# Relay_4_Channel.net
KiCad netlist of a schematic drawn in EAGLE
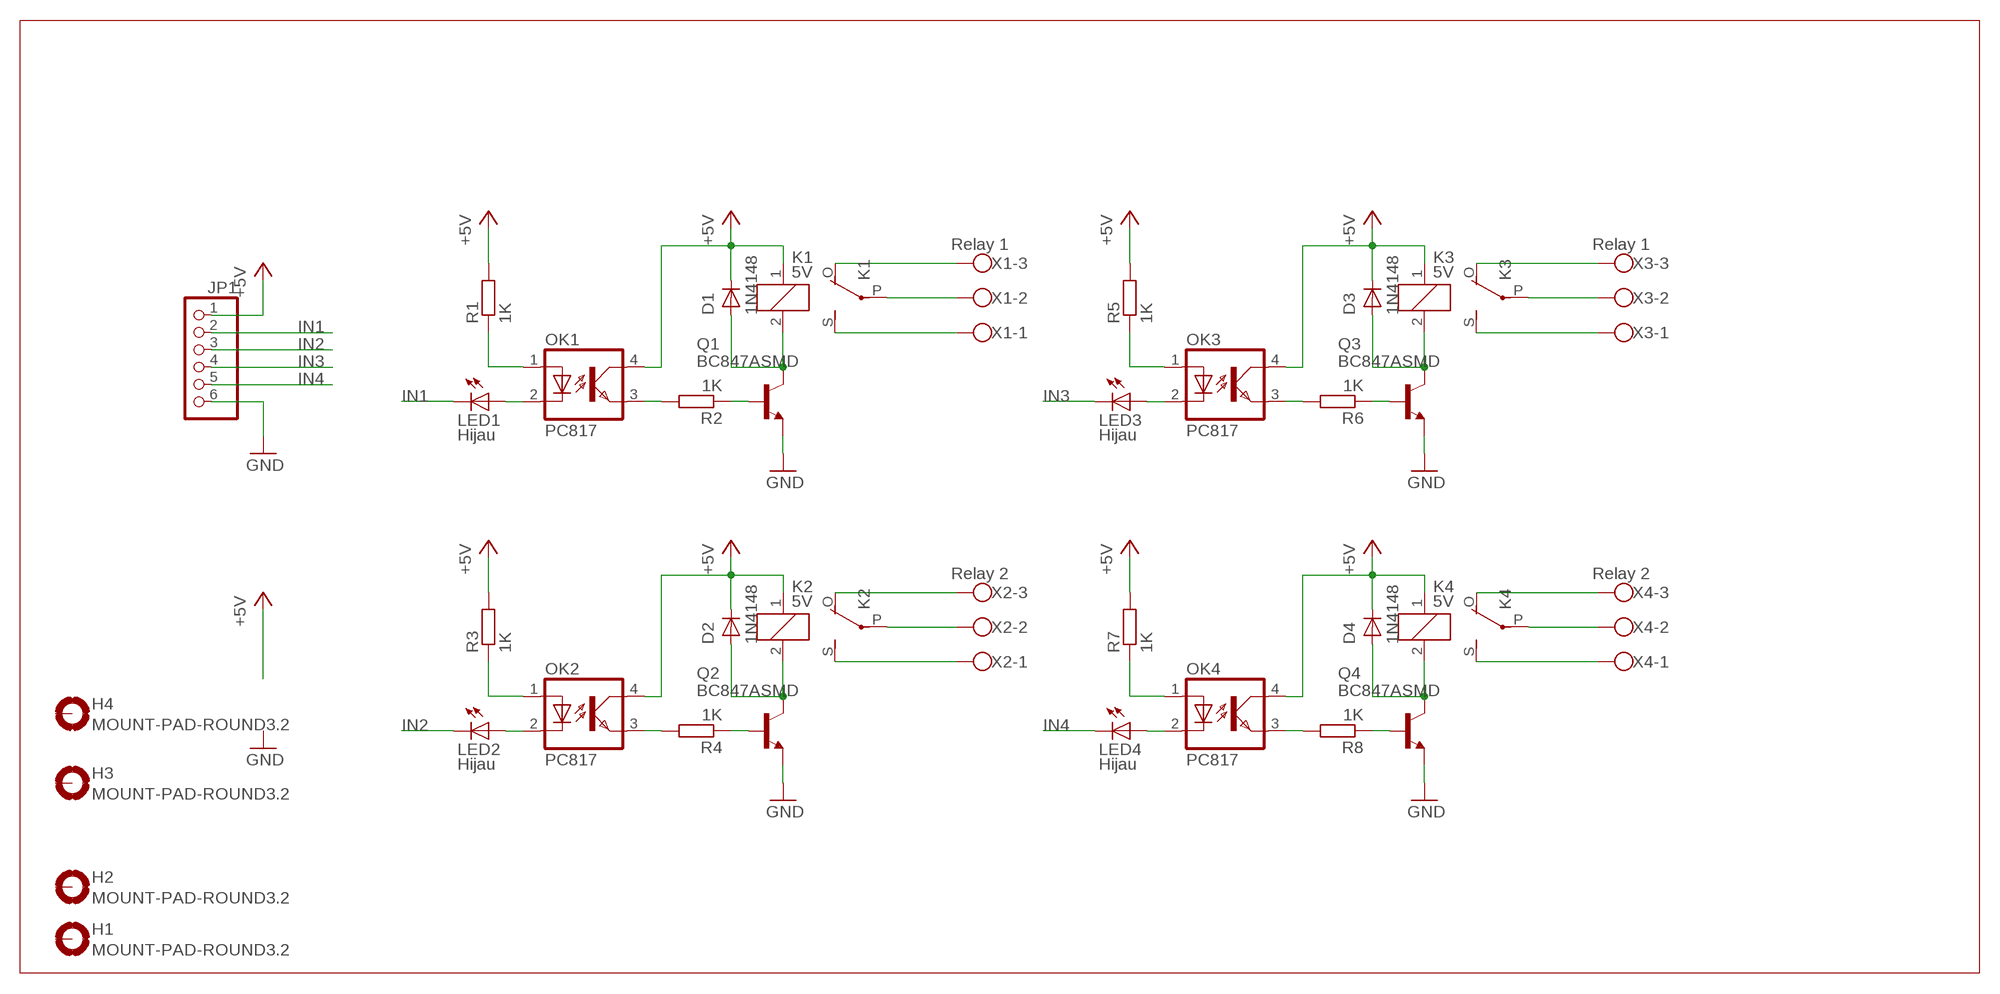
[diagram p0: schematic, sheet 1]

(export (version "E")
  (design (tool "Eeschema 10.0.6"))
  (components
    (comp (ref "D1")
      (value "1N4148")
      (footprint "eagle-import:SMA-DO214AC")
      (libsource (lib "eagle-import") (part "GF1"))
    )
    (comp (ref "D2")
      (value "1N4148")
      (footprint "eagle-import:SMA-DO214AC")
      (libsource (lib "eagle-import") (part "GF1"))
    )
    (comp (ref "D3")
      (value "1N4148")
      (footprint "eagle-import:SMA-DO214AC")
      (libsource (lib "eagle-import") (part "GF1"))
    )
    (comp (ref "D4")
      (value "1N4148")
      (footprint "eagle-import:SMA-DO214AC")
      (libsource (lib "eagle-import") (part "GF1"))
    )
    (comp (ref "H1")
      (value "MOUNT-PAD-ROUND3.2")
      (footprint "eagle-import:3,2-PAD")
      (libsource (lib "eagle-import") (part "MOUNT-PAD-ROUND3.2"))
    )
    (comp (ref "H2")
      (value "MOUNT-PAD-ROUND3.2")
      (footprint "eagle-import:3,2-PAD")
      (libsource (lib "eagle-import") (part "MOUNT-PAD-ROUND3.2"))
    )
    (comp (ref "H3")
      (value "MOUNT-PAD-ROUND3.2")
      (footprint "eagle-import:3,2-PAD")
      (libsource (lib "eagle-import") (part "MOUNT-PAD-ROUND3.2"))
    )
    (comp (ref "H4")
      (value "MOUNT-PAD-ROUND3.2")
      (footprint "eagle-import:3,2-PAD")
      (libsource (lib "eagle-import") (part "MOUNT-PAD-ROUND3.2"))
    )
    (comp (ref "JP1")
      (value "PINHD-1X6")
      (footprint "eagle-import:1X06")
      (libsource (lib "eagle-import") (part "PINHD-1X6"))
    )
    (comp (ref "K1")
      (value "5V")
      (footprint "eagle-import:ZF112")
      (libsource (lib "eagle-import") (part "ZF112"))
    )
    (comp (ref "K2")
      (value "5V")
      (footprint "eagle-import:ZF112")
      (libsource (lib "eagle-import") (part "ZF112"))
    )
    (comp (ref "K3")
      (value "5V")
      (footprint "eagle-import:ZF112")
      (libsource (lib "eagle-import") (part "ZF112"))
    )
    (comp (ref "K4")
      (value "5V")
      (footprint "eagle-import:ZF112")
      (libsource (lib "eagle-import") (part "ZF112"))
    )
    (comp (ref "LED1")
      (value "Hijau")
      (footprint "eagle-import:LED3MM")
      (libsource (lib "eagle-import") (part "LED3MM"))
    )
    (comp (ref "LED2")
      (value "Hijau")
      (footprint "eagle-import:LED3MM")
      (libsource (lib "eagle-import") (part "LED3MM"))
    )
    (comp (ref "LED3")
      (value "Hijau")
      (footprint "eagle-import:LED3MM")
      (libsource (lib "eagle-import") (part "LED3MM"))
    )
    (comp (ref "LED4")
      (value "Hijau")
      (footprint "eagle-import:LED3MM")
      (libsource (lib "eagle-import") (part "LED3MM"))
    )
    (comp (ref "OK1")
      (value "PC817")
      (footprint "eagle-import:DIL04")
      (fields (field (name "MPN") "PC817X4J000F"))
      (libsource (lib "eagle-import") (part "PC817"))
    )
    (comp (ref "OK2")
      (value "PC817")
      (footprint "eagle-import:DIL04")
      (fields (field (name "MPN") "PC817X4J000F"))
      (libsource (lib "eagle-import") (part "PC817"))
    )
    (comp (ref "OK3")
      (value "PC817")
      (footprint "eagle-import:DIL04")
      (fields (field (name "MPN") "PC817X4J000F"))
      (libsource (lib "eagle-import") (part "PC817"))
    )
    (comp (ref "OK4")
      (value "PC817")
      (footprint "eagle-import:DIL04")
      (fields (field (name "MPN") "PC817X4J000F"))
      (libsource (lib "eagle-import") (part "PC817"))
    )
    (comp (ref "Q1")
      (value "BC847ASMD")
      (footprint "eagle-import:SOT23")
      (libsource (lib "eagle-import") (part "BC847SMDA"))
    )
    (comp (ref "Q2")
      (value "BC847ASMD")
      (footprint "eagle-import:SOT23")
      (libsource (lib "eagle-import") (part "BC847SMDA"))
    )
    (comp (ref "Q3")
      (value "BC847ASMD")
      (footprint "eagle-import:SOT23")
      (libsource (lib "eagle-import") (part "BC847SMDA"))
    )
    (comp (ref "Q4")
      (value "BC847ASMD")
      (footprint "eagle-import:SOT23")
      (libsource (lib "eagle-import") (part "BC847SMDA"))
    )
    (comp (ref "R1")
      (value "1K")
      (footprint "eagle-import:R1206")
      (libsource (lib "eagle-import") (part "R-EU_R1206"))
    )
    (comp (ref "R2")
      (value "1K")
      (footprint "eagle-import:R1206")
      (libsource (lib "eagle-import") (part "R-EU_R1206"))
    )
    (comp (ref "R3")
      (value "1K")
      (footprint "eagle-import:R1206")
      (libsource (lib "eagle-import") (part "R-EU_R1206"))
    )
    (comp (ref "R4")
      (value "1K")
      (footprint "eagle-import:R1206")
      (libsource (lib "eagle-import") (part "R-EU_R1206"))
    )
    (comp (ref "R5")
      (value "1K")
      (footprint "eagle-import:R1206")
      (libsource (lib "eagle-import") (part "R-EU_R1206"))
    )
    (comp (ref "R6")
      (value "1K")
      (footprint "eagle-import:R1206")
      (libsource (lib "eagle-import") (part "R-EU_R1206"))
    )
    (comp (ref "R7")
      (value "1K")
      (footprint "eagle-import:R1206")
      (libsource (lib "eagle-import") (part "R-EU_R1206"))
    )
    (comp (ref "R8")
      (value "1K")
      (footprint "eagle-import:R1206")
      (libsource (lib "eagle-import") (part "R-EU_R1206"))
    )
    (comp (ref "X1")
      (value "Relay 1")
      (footprint "eagle-import:W237-103")
      (fields (field (name "MPN") "237-103"))
      (libsource (lib "eagle-import") (part "W237-103"))
    )
    (comp (ref "X2")
      (value "Relay 2")
      (footprint "eagle-import:W237-103")
      (fields (field (name "MPN") "237-103"))
      (libsource (lib "eagle-import") (part "W237-103"))
    )
    (comp (ref "X3")
      (value "Relay 1")
      (footprint "eagle-import:W237-103")
      (fields (field (name "MPN") "237-103"))
      (libsource (lib "eagle-import") (part "W237-103"))
    )
    (comp (ref "X4")
      (value "Relay 2")
      (footprint "eagle-import:W237-103")
      (fields (field (name "MPN") "237-103"))
      (libsource (lib "eagle-import") (part "W237-103"))
    )
  )
  (nets
    (net (code "1") (name "+5V") (class "Default")
      (node (ref "D1") (pin "K") (pinfunction "C_K") (pintype "passive"))
      (node (ref "D2") (pin "K") (pinfunction "C_K") (pintype "passive"))
      (node (ref "D3") (pin "K") (pinfunction "C_K") (pintype "passive"))
      (node (ref "D4") (pin "K") (pinfunction "C_K") (pintype "passive"))
      (node (ref "JP1") (pin "1") (pinfunction "1_1") (pintype "passive"))
      (node (ref "K1") (pin "1") (pinfunction "1_1") (pintype "passive"))
      (node (ref "K2") (pin "1") (pinfunction "1_1") (pintype "passive"))
      (node (ref "K3") (pin "1") (pinfunction "1_1") (pintype "passive"))
      (node (ref "K4") (pin "1") (pinfunction "1_1") (pintype "passive"))
      (node (ref "OK1") (pin "4") (pinfunction "COL_4") (pintype "passive"))
      (node (ref "OK2") (pin "4") (pinfunction "COL_4") (pintype "passive"))
      (node (ref "OK3") (pin "4") (pinfunction "COL_4") (pintype "passive"))
      (node (ref "OK4") (pin "4") (pinfunction "COL_4") (pintype "passive"))
      (node (ref "R1") (pin "2") (pinfunction "2_2") (pintype "passive"))
      (node (ref "R3") (pin "2") (pinfunction "2_2") (pintype "passive"))
      (node (ref "R5") (pin "2") (pinfunction "2_2") (pintype "passive"))
      (node (ref "R7") (pin "2") (pinfunction "2_2") (pintype "passive"))
    )
    (net (code "2") (name "/IN1") (class "Default")
      (node (ref "JP1") (pin "2") (pinfunction "2_2") (pintype "passive"))
      (node (ref "LED1") (pin "K") (pinfunction "C_K") (pintype "passive"))
    )
    (net (code "3") (name "/IN2") (class "Default")
      (node (ref "JP1") (pin "3") (pinfunction "3_3") (pintype "passive"))
      (node (ref "LED2") (pin "K") (pinfunction "C_K") (pintype "passive"))
    )
    (net (code "4") (name "/IN3") (class "Default")
      (node (ref "JP1") (pin "4") (pinfunction "4_4") (pintype "passive"))
      (node (ref "LED3") (pin "K") (pinfunction "C_K") (pintype "passive"))
    )
    (net (code "5") (name "/IN4") (class "Default")
      (node (ref "JP1") (pin "5") (pinfunction "5_5") (pintype "passive"))
      (node (ref "LED4") (pin "K") (pinfunction "C_K") (pintype "passive"))
    )
    (net (code "6") (name "GND") (class "Default")
      (node (ref "JP1") (pin "6") (pinfunction "6_6") (pintype "passive"))
      (node (ref "Q1") (pin "2") (pinfunction "E_2") (pintype "passive"))
      (node (ref "Q2") (pin "2") (pinfunction "E_2") (pintype "passive"))
      (node (ref "Q3") (pin "2") (pinfunction "E_2") (pintype "passive"))
      (node (ref "Q4") (pin "2") (pinfunction "E_2") (pintype "passive"))
    )
    (net (code "7") (name "Net-(OK1-A)") (class "Default")
      (node (ref "OK1") (pin "1") (pinfunction "A_1") (pintype "passive"))
      (node (ref "R1") (pin "1") (pinfunction "1_1") (pintype "passive"))
    )
    (net (code "8") (name "Net-(OK1-C)") (class "Default")
      (node (ref "LED1") (pin "A") (pinfunction "A_A") (pintype "passive"))
      (node (ref "OK1") (pin "2") (pinfunction "C_2") (pintype "passive"))
    )
    (net (code "9") (name "Net-(OK1-EMIT)") (class "Default")
      (node (ref "OK1") (pin "3") (pinfunction "EMIT_3") (pintype "passive"))
      (node (ref "R2") (pin "2") (pinfunction "2_2") (pintype "passive"))
    )
    (net (code "10") (name "Net-(OK2-A)") (class "Default")
      (node (ref "OK2") (pin "1") (pinfunction "A_1") (pintype "passive"))
      (node (ref "R3") (pin "1") (pinfunction "1_1") (pintype "passive"))
    )
    (net (code "11") (name "Net-(OK2-C)") (class "Default")
      (node (ref "LED2") (pin "A") (pinfunction "A_A") (pintype "passive"))
      (node (ref "OK2") (pin "2") (pinfunction "C_2") (pintype "passive"))
    )
    (net (code "12") (name "Net-(OK2-EMIT)") (class "Default")
      (node (ref "OK2") (pin "3") (pinfunction "EMIT_3") (pintype "passive"))
      (node (ref "R4") (pin "2") (pinfunction "2_2") (pintype "passive"))
    )
    (net (code "13") (name "Net-(OK3-A)") (class "Default")
      (node (ref "OK3") (pin "1") (pinfunction "A_1") (pintype "passive"))
      (node (ref "R5") (pin "1") (pinfunction "1_1") (pintype "passive"))
    )
    (net (code "14") (name "Net-(OK3-C)") (class "Default")
      (node (ref "LED3") (pin "A") (pinfunction "A_A") (pintype "passive"))
      (node (ref "OK3") (pin "2") (pinfunction "C_2") (pintype "passive"))
    )
    (net (code "15") (name "Net-(OK3-EMIT)") (class "Default")
      (node (ref "OK3") (pin "3") (pinfunction "EMIT_3") (pintype "passive"))
      (node (ref "R6") (pin "2") (pinfunction "2_2") (pintype "passive"))
    )
    (net (code "16") (name "Net-(OK4-A)") (class "Default")
      (node (ref "OK4") (pin "1") (pinfunction "A_1") (pintype "passive"))
      (node (ref "R7") (pin "1") (pinfunction "1_1") (pintype "passive"))
    )
    (net (code "17") (name "Net-(OK4-C)") (class "Default")
      (node (ref "LED4") (pin "A") (pinfunction "A_A") (pintype "passive"))
      (node (ref "OK4") (pin "2") (pinfunction "C_2") (pintype "passive"))
    )
    (net (code "18") (name "Net-(OK4-EMIT)") (class "Default")
      (node (ref "OK4") (pin "3") (pinfunction "EMIT_3") (pintype "passive"))
      (node (ref "R8") (pin "2") (pinfunction "2_2") (pintype "passive"))
    )
    (net (code "19") (name "Net-(Q1-B)") (class "Default")
      (node (ref "Q1") (pin "1") (pinfunction "B_1") (pintype "passive"))
      (node (ref "R2") (pin "1") (pinfunction "1_1") (pintype "passive"))
    )
    (net (code "20") (name "Net-(Q1-C)") (class "Default")
      (node (ref "D1") (pin "A") (pinfunction "A_A") (pintype "passive"))
      (node (ref "K1") (pin "2") (pinfunction "2_2") (pintype "passive"))
      (node (ref "Q1") (pin "3") (pinfunction "C_3") (pintype "passive"))
    )
    (net (code "21") (name "Net-(Q2-B)") (class "Default")
      (node (ref "Q2") (pin "1") (pinfunction "B_1") (pintype "passive"))
      (node (ref "R4") (pin "1") (pinfunction "1_1") (pintype "passive"))
    )
    (net (code "22") (name "Net-(Q2-C)") (class "Default")
      (node (ref "D2") (pin "A") (pinfunction "A_A") (pintype "passive"))
      (node (ref "K2") (pin "2") (pinfunction "2_2") (pintype "passive"))
      (node (ref "Q2") (pin "3") (pinfunction "C_3") (pintype "passive"))
    )
    (net (code "23") (name "Net-(Q3-B)") (class "Default")
      (node (ref "Q3") (pin "1") (pinfunction "B_1") (pintype "passive"))
      (node (ref "R6") (pin "1") (pinfunction "1_1") (pintype "passive"))
    )
    (net (code "24") (name "Net-(Q3-C)") (class "Default")
      (node (ref "D3") (pin "A") (pinfunction "A_A") (pintype "passive"))
      (node (ref "K3") (pin "2") (pinfunction "2_2") (pintype "passive"))
      (node (ref "Q3") (pin "3") (pinfunction "C_3") (pintype "passive"))
    )
    (net (code "25") (name "Net-(Q4-B)") (class "Default")
      (node (ref "Q4") (pin "1") (pinfunction "B_1") (pintype "passive"))
      (node (ref "R8") (pin "1") (pinfunction "1_1") (pintype "passive"))
    )
    (net (code "26") (name "Net-(Q4-C)") (class "Default")
      (node (ref "D4") (pin "A") (pinfunction "A_A") (pintype "passive"))
      (node (ref "K4") (pin "2") (pinfunction "2_2") (pintype "passive"))
      (node (ref "Q4") (pin "3") (pinfunction "C_3") (pintype "passive"))
    )
    (net (code "27") (name "Net-(X1A-KL)") (class "Default")
      (node (ref "K1") (pin "S") (pinfunction "S_S") (pintype "passive"))
      (node (ref "X1") (pin "1") (pinfunction "KL_1") (pintype "passive"))
    )
    (net (code "28") (name "Net-(X1B-KL)") (class "Default")
      (node (ref "K1") (pin "P") (pinfunction "P_P") (pintype "passive"))
      (node (ref "X1") (pin "2") (pinfunction "KL_2") (pintype "passive"))
    )
    (net (code "29") (name "Net-(X1C-KL)") (class "Default")
      (node (ref "K1") (pin "O") (pinfunction "O_O") (pintype "passive"))
      (node (ref "X1") (pin "3") (pinfunction "KL_3") (pintype "passive"))
    )
    (net (code "30") (name "Net-(X2A-KL)") (class "Default")
      (node (ref "K2") (pin "S") (pinfunction "S_S") (pintype "passive"))
      (node (ref "X2") (pin "1") (pinfunction "KL_1") (pintype "passive"))
    )
    (net (code "31") (name "Net-(X2B-KL)") (class "Default")
      (node (ref "K2") (pin "P") (pinfunction "P_P") (pintype "passive"))
      (node (ref "X2") (pin "2") (pinfunction "KL_2") (pintype "passive"))
    )
    (net (code "32") (name "Net-(X2C-KL)") (class "Default")
      (node (ref "K2") (pin "O") (pinfunction "O_O") (pintype "passive"))
      (node (ref "X2") (pin "3") (pinfunction "KL_3") (pintype "passive"))
    )
    (net (code "33") (name "Net-(X3A-KL)") (class "Default")
      (node (ref "K3") (pin "S") (pinfunction "S_S") (pintype "passive"))
      (node (ref "X3") (pin "1") (pinfunction "KL_1") (pintype "passive"))
    )
    (net (code "34") (name "Net-(X3B-KL)") (class "Default")
      (node (ref "K3") (pin "P") (pinfunction "P_P") (pintype "passive"))
      (node (ref "X3") (pin "2") (pinfunction "KL_2") (pintype "passive"))
    )
    (net (code "35") (name "Net-(X3C-KL)") (class "Default")
      (node (ref "K3") (pin "O") (pinfunction "O_O") (pintype "passive"))
      (node (ref "X3") (pin "3") (pinfunction "KL_3") (pintype "passive"))
    )
    (net (code "36") (name "Net-(X4A-KL)") (class "Default")
      (node (ref "K4") (pin "S") (pinfunction "S_S") (pintype "passive"))
      (node (ref "X4") (pin "1") (pinfunction "KL_1") (pintype "passive"))
    )
    (net (code "37") (name "Net-(X4B-KL)") (class "Default")
      (node (ref "K4") (pin "P") (pinfunction "P_P") (pintype "passive"))
      (node (ref "X4") (pin "2") (pinfunction "KL_2") (pintype "passive"))
    )
    (net (code "38") (name "Net-(X4C-KL)") (class "Default")
      (node (ref "K4") (pin "O") (pinfunction "O_O") (pintype "passive"))
      (node (ref "X4") (pin "3") (pinfunction "KL_3") (pintype "passive"))
    )
    (net (code "39") (name "unconnected-(H1-MOUNT-PadB3,2)") (class "Default")
      (node (ref "H1") (pin "B3,2") (pinfunction "MOUNT_B3,2") (pintype "passive"))
    )
    (net (code "40") (name "unconnected-(H2-MOUNT-PadB3,2)") (class "Default")
      (node (ref "H2") (pin "B3,2") (pinfunction "MOUNT_B3,2") (pintype "passive"))
    )
    (net (code "41") (name "unconnected-(H3-MOUNT-PadB3,2)") (class "Default")
      (node (ref "H3") (pin "B3,2") (pinfunction "MOUNT_B3,2") (pintype "passive"))
    )
    (net (code "42") (name "unconnected-(H4-MOUNT-PadB3,2)") (class "Default")
      (node (ref "H4") (pin "B3,2") (pinfunction "MOUNT_B3,2") (pintype "passive"))
    )
  )
)
